# half-pint-turbidimeter_controls_2_0_1.net
KiCad netlist of a schematic drawn in EAGLE
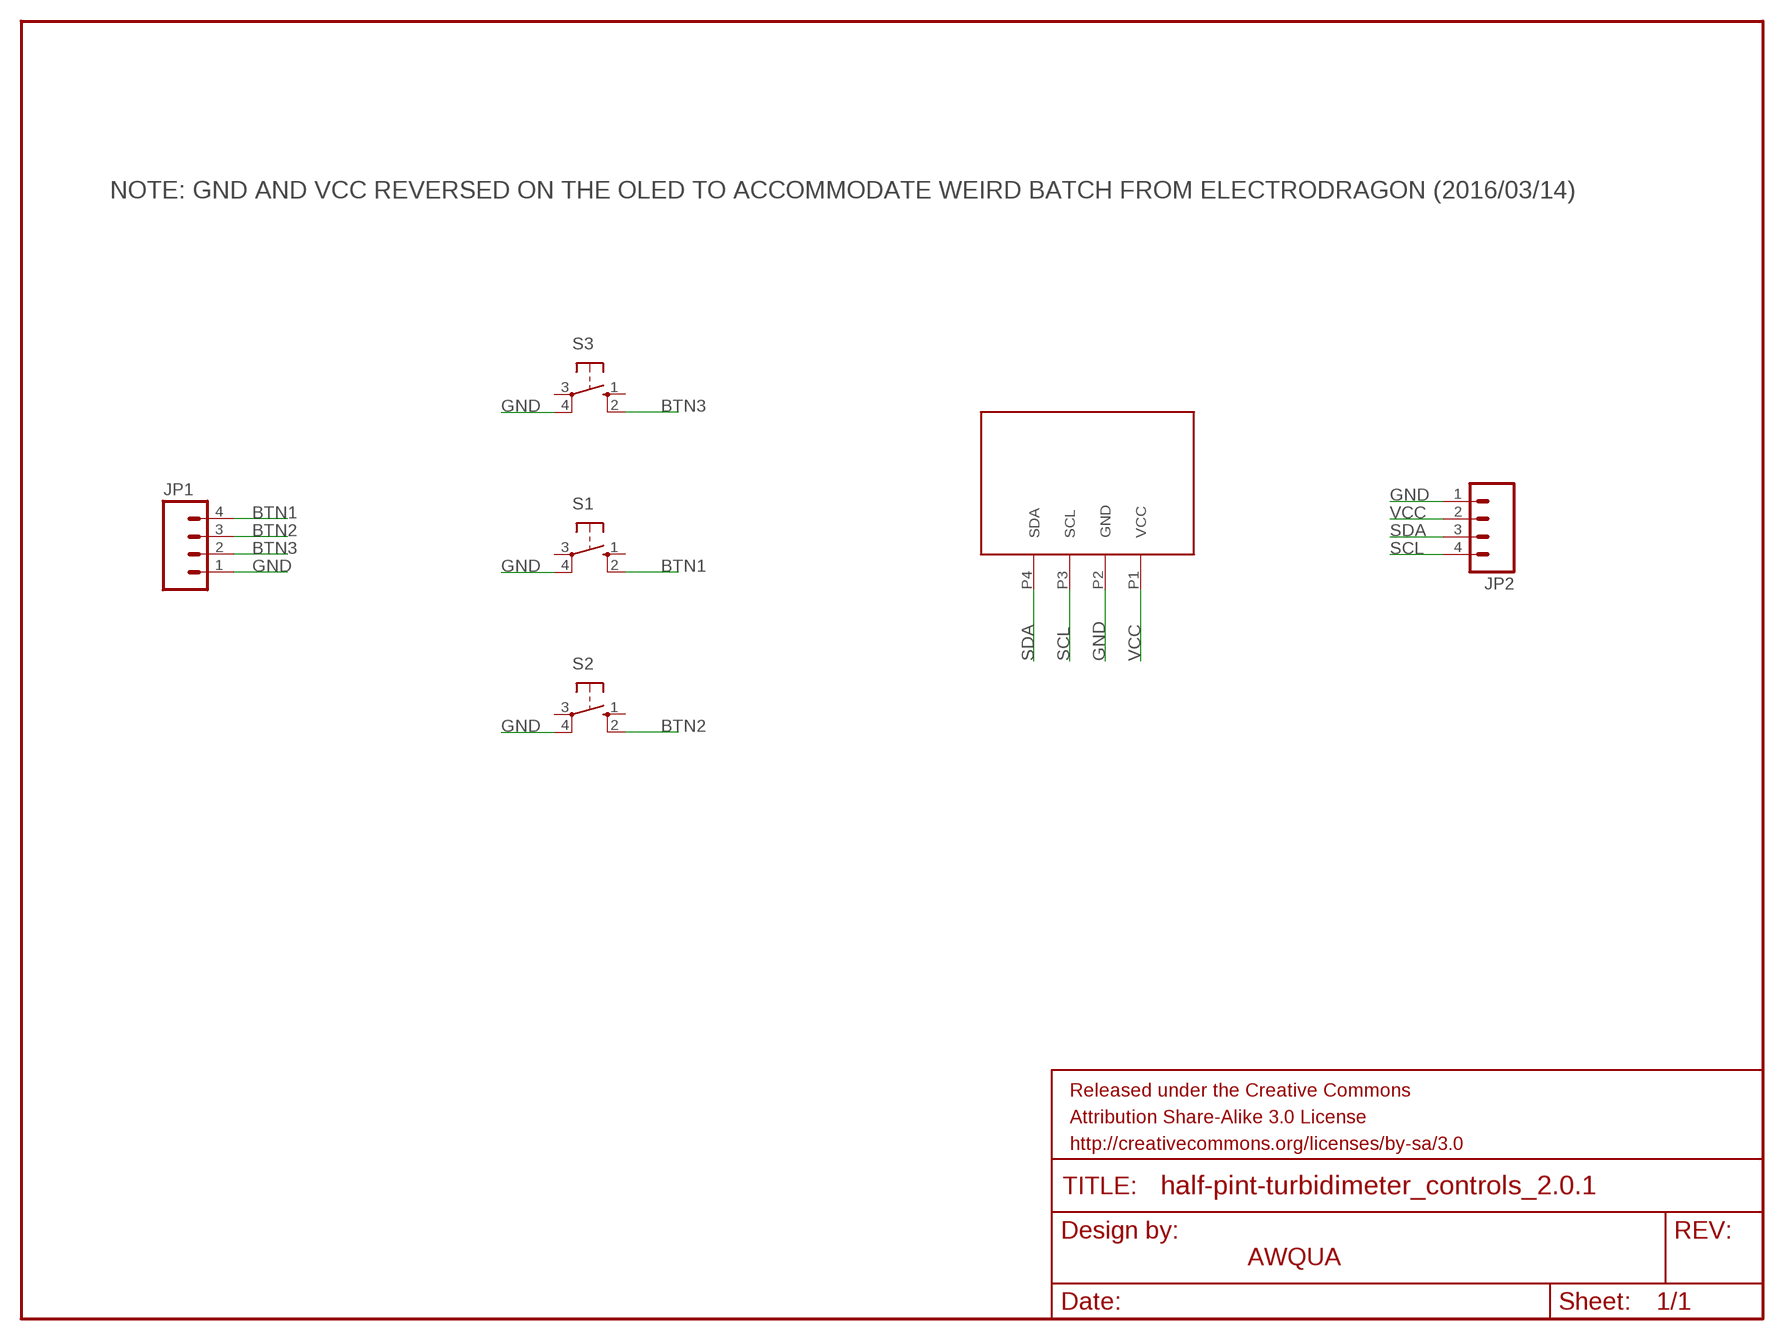
[diagram p0: schematic, sheet 1]

(export (version "E")
  (design (tool "Eeschema 10.0.6"))
  (components
    (comp (ref "FRAME1")
      (value "FRAME-LETTER")
      (footprint "eagle-import:CREATIVE_COMMONS")
      (libsource (lib "eagle-import") (part "FRAME-LETTER"))
    )
    (comp (ref "JP1")
      (value "M04PTH")
      (footprint "eagle-import:1X04")
      (libsource (lib "eagle-import") (part "M04PTH"))
    )
    (comp (ref "JP2")
      (value "M04PTH")
      (footprint "eagle-import:1X04")
      (libsource (lib "eagle-import") (part "M04PTH"))
    )
    (comp (ref "S1")
      (value "40-XX")
      (footprint "eagle-import:B3F-40XX")
      (fields (field (name "MF") "OMRON COMPONENTS USA") (field (name "MPN") "B3F-4000"))
      (libsource (lib "eagle-import") (part "40-XX"))
    )
    (comp (ref "S2")
      (value "40-XX")
      (footprint "eagle-import:B3F-40XX")
      (fields (field (name "MF") "OMRON COMPONENTS USA") (field (name "MPN") "B3F-4000"))
      (libsource (lib "eagle-import") (part "40-XX"))
    )
    (comp (ref "S3")
      (value "40-XX")
      (footprint "eagle-import:B3F-40XX")
      (fields (field (name "MF") "OMRON COMPONENTS USA") (field (name "MPN") "B3F-4000"))
      (libsource (lib "eagle-import") (part "40-XX"))
    )
    (comp (ref "U$2")
      (value "I2C-OLED-096")
      (footprint "eagle-import:I2C-OLED-096")
      (libsource (lib "eagle-import") (part "I2C-OLED-096"))
    )
  )
  (nets
    (net (code "1") (name "/BTN1") (class "Default")
      (node (ref "JP1") (pin "4") (pinfunction "4_4") (pintype "passive"))
      (node (ref "S1") (pin "2") (pinfunction "S1_2") (pintype "passive"))
    )
    (net (code "2") (name "/BTN2") (class "Default")
      (node (ref "JP1") (pin "3") (pinfunction "3_3") (pintype "passive"))
      (node (ref "S2") (pin "2") (pinfunction "S1_2") (pintype "passive"))
    )
    (net (code "3") (name "/BTN3") (class "Default")
      (node (ref "JP1") (pin "2") (pinfunction "2_2") (pintype "passive"))
      (node (ref "S3") (pin "2") (pinfunction "S1_2") (pintype "passive"))
    )
    (net (code "4") (name "/GND") (class "Default")
      (node (ref "JP1") (pin "1") (pinfunction "1_1") (pintype "passive"))
      (node (ref "JP2") (pin "1") (pinfunction "1_1") (pintype "passive"))
      (node (ref "S1") (pin "4") (pinfunction "P1_4") (pintype "passive"))
      (node (ref "S2") (pin "4") (pinfunction "P1_4") (pintype "passive"))
      (node (ref "S3") (pin "4") (pinfunction "P1_4") (pintype "passive"))
      (node (ref "U$2") (pin "P2") (pinfunction "GND_P2") (pintype "bidirectional"))
    )
    (net (code "5") (name "/SCL") (class "Default")
      (node (ref "JP2") (pin "4") (pinfunction "4_4") (pintype "passive"))
      (node (ref "U$2") (pin "P3") (pinfunction "SCL_P3") (pintype "bidirectional"))
    )
    (net (code "6") (name "/SDA") (class "Default")
      (node (ref "JP2") (pin "3") (pinfunction "3_3") (pintype "passive"))
      (node (ref "U$2") (pin "P4") (pinfunction "SDA_P4") (pintype "bidirectional"))
    )
    (net (code "7") (name "/VCC") (class "Default")
      (node (ref "JP2") (pin "2") (pinfunction "2_2") (pintype "passive"))
      (node (ref "U$2") (pin "P1") (pinfunction "VCC_P1") (pintype "bidirectional"))
    )
    (net (code "8") (name "unconnected-(S1-P-Pad3)") (class "Default")
      (node (ref "S1") (pin "3") (pinfunction "P_3") (pintype "passive"))
    )
    (net (code "9") (name "unconnected-(S1-S-Pad1)") (class "Default")
      (node (ref "S1") (pin "1") (pinfunction "S_1") (pintype "passive"))
    )
    (net (code "10") (name "unconnected-(S2-P-Pad3)") (class "Default")
      (node (ref "S2") (pin "3") (pinfunction "P_3") (pintype "passive"))
    )
    (net (code "11") (name "unconnected-(S2-S-Pad1)") (class "Default")
      (node (ref "S2") (pin "1") (pinfunction "S_1") (pintype "passive"))
    )
    (net (code "12") (name "unconnected-(S3-P-Pad3)") (class "Default")
      (node (ref "S3") (pin "3") (pinfunction "P_3") (pintype "passive"))
    )
    (net (code "13") (name "unconnected-(S3-S-Pad1)") (class "Default")
      (node (ref "S3") (pin "1") (pinfunction "S_1") (pintype "passive"))
    )
  )
)
